# LD1117.net
KiCad netlist of a schematic drawn in Altium Designer
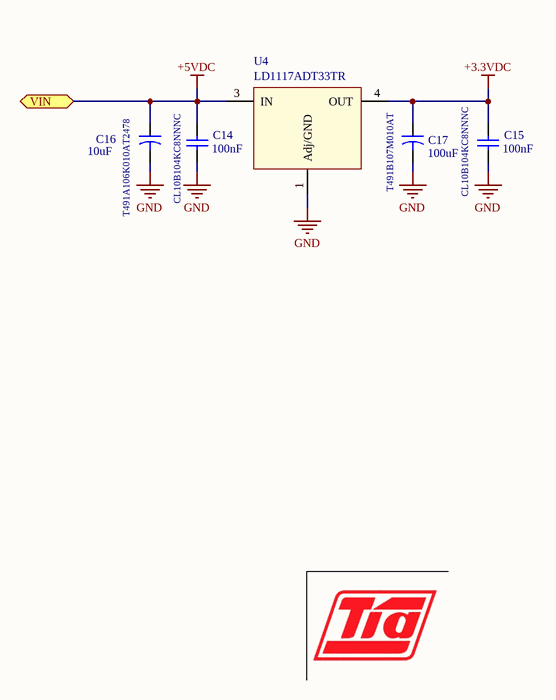
[diagram p0: LD1117.SchDoc]

(export (version "E")
  (design (tool "Eeschema 10.0.6"))
  (components
    (comp (ref "C14")
      (value "CL10B104KC8NNNC")
      (footprint "C0603C104K5RACTU")
      (fields (field (name "ALTIUM_VALUE") "100nF") (field (name "LCSC PART") "C15725"))
      (libsource (lib "IDETEC LIB") (part "Cap 100nF (0603)"))
    )
    (comp (ref "C15")
      (value "CL10B104KC8NNNC")
      (footprint "C0603C104K5RACTU")
      (fields (field (name "ALTIUM_VALUE") "100nF") (field (name "LCSC PART") "C15725"))
      (libsource (lib "IDETEC LIB") (part "Cap 100nF (0603)"))
    )
    (comp (ref "C16")
      (value "T491A106K010AT2478")
      (footprint "3216 Case-A")
      (description "CAP TANT 10UF 6.3V 20% 1206")
      (fields (field (name "ALTIUM_VALUE") "10uF") (field (name "LCSC PART") "C110052"))
      (libsource (lib "IDETEC LIB") (part "T491A106M006AT"))
    )
    (comp (ref "C17")
      (value "T491B107M010AT")
      (footprint "TAJB107M006RNJ")
      (description "Capacitor")
      (fields (field (name "ALTIUM_VALUE") "100uF") (field (name "LCSC PART") "C90975"))
      (libsource (lib "IDETEC LIB") (part "Cap 10uF (C3216)"))
    )
    (comp (ref "U4")
      (value "LD1117ADT33TR")
      (footprint "TO252")
      (description "800mA Low-Dropout Linear Regulator")
      (fields (field (name "MANUFACTURER") "National Semiconductor") (field (name "LCSC PART") "C157401"))
      (libsource (lib "TSK Library") (part "LM1117DT"))
    )
  )
  (nets
    (net (code "1") (name "+3.3VDC") (class "Default")
      (node (ref "C15") (pin "2") (pinfunction "2_2") (pintype "passive"))
      (node (ref "C17") (pin "1") (pinfunction "1_1") (pintype "passive"))
      (node (ref "U4") (pin "4") (pinfunction "OUT_4") (pintype "passive"))
    )
    (net (code "2") (name "+5VDC") (class "Default")
      (node (ref "C14") (pin "2") (pinfunction "2_2") (pintype "passive"))
      (node (ref "C16") (pin "1") (pinfunction "1_1") (pintype "passive"))
      (node (ref "U4") (pin "3") (pinfunction "IN_3") (pintype "passive"))
    )
    (net (code "3") (name "GND") (class "Default")
      (node (ref "C14") (pin "1") (pinfunction "1_1") (pintype "passive"))
      (node (ref "C15") (pin "1") (pinfunction "1_1") (pintype "passive"))
      (node (ref "C16") (pin "2") (pinfunction "2_2") (pintype "passive"))
      (node (ref "C17") (pin "2") (pinfunction "2_2") (pintype "passive"))
      (node (ref "U4") (pin "1") (pinfunction "Adj/GND_1") (pintype "passive"))
    )
  )
)
